# 1_8V.net
KiCad netlist of a schematic drawn in Altium Designer
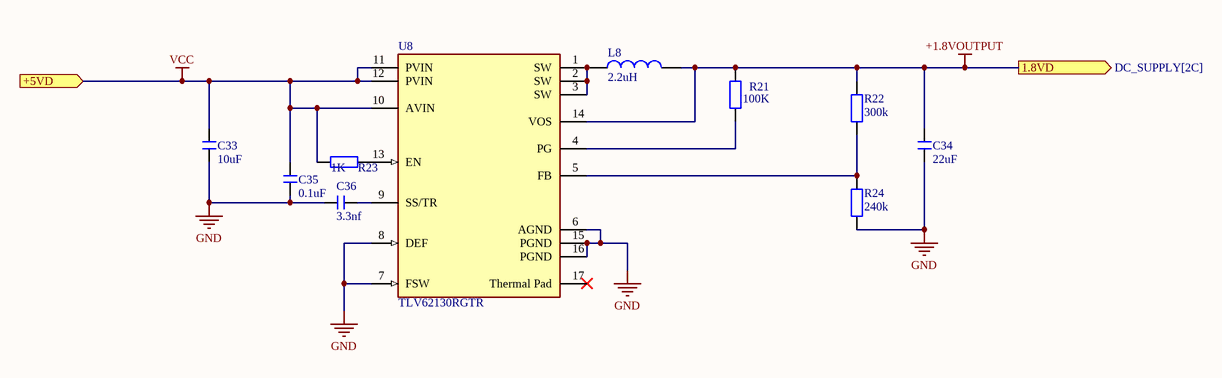
[diagram p0: 1.8V.SchDoc]

(export (version "E")
  (design (tool "Eeschema 10.0.6"))
  (components
    (comp (ref "C33")
      (value "10uF")
      (footprint "C 0805_L")
      (description "贴片电容 10 µF, 25 V, Ceramic, 1210")
      (libsource (lib "0.1 - 电阻-电容-电感") (part "C"))
    )
    (comp (ref "C34")
      (value "22uF")
      (footprint "C 0805_L")
      (description "贴片电容 22 µF, 6.3 V, Ceramic, 0805")
      (libsource (lib "0.1 - 电阻-电容-电感") (part "C"))
    )
    (comp (ref "C35")
      (value "0.1uF")
      (footprint "C 0805_L")
      (description "贴片电容")
      (libsource (lib "0.1 - 电阻-电容-电感") (part "C"))
    )
    (comp (ref "C36")
      (value "3.3nf")
      (footprint "C 0805_L")
      (description "贴片电容 3300 pF, 25 V, Ceramic, 0603")
      (libsource (lib "0.1 - 电阻-电容-电感") (part "C"))
    )
    (comp (ref "L8")
      (value "2.2uH")
      (footprint "L 0805")
      (description "小功率贴片电感")
      (libsource (lib "0.1 - 电阻-电容-电感") (part "L"))
    )
    (comp (ref "R21")
      (value "100K")
      (footprint "R 0805_L")
      (description "贴片电阻")
      (fields (field (name "版权归属") "来自淘宝 ID：黄晶宝石"))
      (libsource (lib "0.1 - 电阻-电容-电感") (part "R"))
    )
    (comp (ref "R22")
      (value "300k")
      (footprint "R 0805_L")
      (description "贴片电阻")
      (fields (field (name "版权归属") "来自淘宝 ID：黄晶宝石"))
      (libsource (lib "0.1 - 电阻-电容-电感") (part "R"))
    )
    (comp (ref "R23")
      (value "1K")
      (footprint "R 0805_L")
      (description "贴片电阻R1 IMPORTANT, TO PREVENT HV DAMAGE")
      (fields (field (name "版权归属") "来自淘宝 ID：黄晶宝石"))
      (libsource (lib "0.1 - 电阻-电容-电感") (part "R"))
    )
    (comp (ref "R24")
      (value "240k")
      (footprint "R 0805_L")
      (description "贴片电阻")
      (fields (field (name "版权归属") "来自淘宝 ID：黄晶宝石"))
      (libsource (lib "0.1 - 电阻-电容-电感") (part "R"))
    )
    (comp (ref "U8")
      (value "TLV62130RGTR")
      (footprint "FP-RGT0016C-IPC_A")
      (description "IC REG BUCK ADJUSTABLE 3A 16QFN")
      (fields
        (field (name "MANUFACTURER") "Texas Instruments")
        (field (name "OCTOPART") "https://octopart.com/tlv62130rgtr-texas+instruments-21766117")
      )
      (libsource (lib "Components - 23.10.23 - 12.36") (part "CMP-04918-000039-1"))
    )
  )
  (nets
    (net (code "1") (name "+1.8VOUTPUT") (class "Default")
      (node (ref "C34") (pin "2") (pinfunction "2_2") (pintype "passive"))
      (node (ref "L8") (pin "2") (pinfunction "2_2") (pintype "passive"))
      (node (ref "R21") (pin "2") (pinfunction "2_2") (pintype "passive"))
      (node (ref "R22") (pin "2") (pinfunction "2_2") (pintype "passive"))
      (node (ref "U8") (pin "14") (pinfunction "VOS_14") (pintype "passive"))
    )
    (net (code "2") (name "GND") (class "Default")
      (node (ref "C33") (pin "1") (pinfunction "1_1") (pintype "passive"))
      (node (ref "C34") (pin "1") (pinfunction "1_1") (pintype "passive"))
      (node (ref "C35") (pin "1") (pinfunction "1_1") (pintype "passive"))
      (node (ref "C36") (pin "1") (pinfunction "1_1") (pintype "passive"))
      (node (ref "R24") (pin "1") (pinfunction "1_1") (pintype "passive"))
      (node (ref "U8") (pin "15") (pinfunction "PGND_15") (pintype "power_in"))
      (node (ref "U8") (pin "16") (pinfunction "PGND_16") (pintype "power_in"))
      (node (ref "U8") (pin "6") (pinfunction "AGND_6") (pintype "power_in"))
      (node (ref "U8") (pin "7") (pinfunction "FSW_7") (pintype "input"))
      (node (ref "U8") (pin "8") (pinfunction "DEF_8") (pintype "input"))
    )
    (net (code "3") (name "Net-(L8-Pad1)") (class "Default")
      (node (ref "L8") (pin "1") (pinfunction "1_1") (pintype "passive"))
      (node (ref "U8") (pin "1") (pinfunction "SW_1") (pintype "passive"))
      (node (ref "U8") (pin "2") (pinfunction "SW_2") (pintype "passive"))
      (node (ref "U8") (pin "3") (pinfunction "SW_3") (pintype "passive"))
    )
    (net (code "4") (name "Net-(U8-EN)") (class "Default")
      (node (ref "R23") (pin "2") (pinfunction "2_2") (pintype "passive"))
      (node (ref "U8") (pin "13") (pinfunction "EN_13") (pintype "input"))
    )
    (net (code "5") (name "Net-(U8-FB)") (class "Default")
      (node (ref "R22") (pin "1") (pinfunction "1_1") (pintype "passive"))
      (node (ref "R24") (pin "2") (pinfunction "2_2") (pintype "passive"))
      (node (ref "U8") (pin "5") (pinfunction "FB_5") (pintype "passive"))
    )
    (net (code "6") (name "Net-(U8-PG)") (class "Default")
      (node (ref "R21") (pin "1") (pinfunction "1_1") (pintype "passive"))
      (node (ref "U8") (pin "4") (pinfunction "PG_4") (pintype "open_collector"))
    )
    (net (code "7") (name "Net-(U8-SS{slash}TR)") (class "Default")
      (node (ref "C36") (pin "2") (pinfunction "2_2") (pintype "passive"))
      (node (ref "U8") (pin "9") (pinfunction "SS/TR_9") (pintype "passive"))
    )
    (net (code "8") (name "VCC") (class "Default")
      (node (ref "C33") (pin "2") (pinfunction "2_2") (pintype "passive"))
      (node (ref "C35") (pin "2") (pinfunction "2_2") (pintype "passive"))
      (node (ref "R23") (pin "1") (pinfunction "1_1") (pintype "passive"))
      (node (ref "U8") (pin "10") (pinfunction "AVIN_10") (pintype "passive"))
      (node (ref "U8") (pin "11") (pinfunction "PVIN_11") (pintype "passive"))
      (node (ref "U8") (pin "12") (pinfunction "PVIN_12") (pintype "passive"))
    )
    (net (code "9") (name "unconnected-(U8-Thermal_Pad-Pad17)") (class "Default")
      (node (ref "U8") (pin "17") (pinfunction "Thermal_Pad_17") (pintype "power_in+no_connect"))
    )
  )
)
